# sheet1.net
KiCad netlist of a schematic drawn in Altium Designer
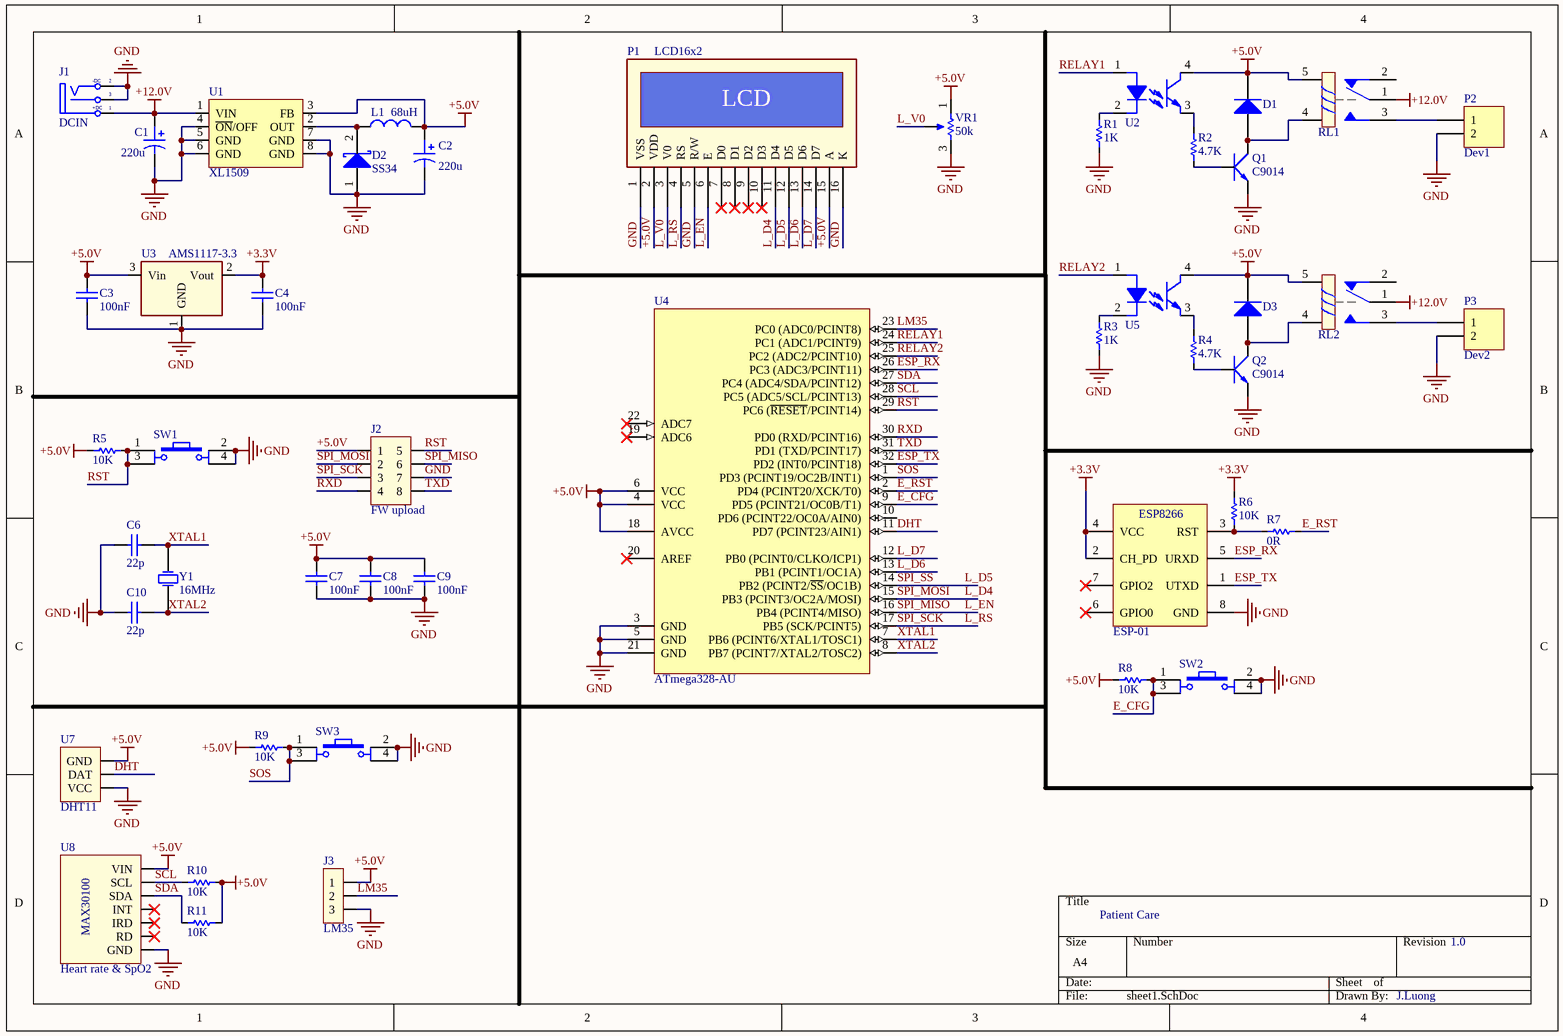
[diagram p0: sheet1.SchDoc]

(export (version "E")
  (design (tool "Eeschema 10.0.6"))
  (components
    (comp (ref "C1")
      (value "220u")
      (footprint "CAP_SMD_7343")
      (description "Polarized Capacitor")
      (fields (field (name "Comment") "Cap Pol") (field (name "PUBLISHER") "Altium Limited"))
      (libsource (lib "jmctvs") (part "Cap Pol"))
    )
    (comp (ref "C2")
      (value "220u")
      (footprint "CAP_SMD_7343")
      (description "Polarized Capacitor")
      (fields (field (name "Comment") "Cap Pol") (field (name "PUBLISHER") "Altium Limited"))
      (libsource (lib "jmctvs") (part "Cap Pol"))
    )
    (comp (ref "C3")
      (value "100nF")
      (footprint "CAP_SMD_0805")
      (description "Non-polarized Capacitor")
      (fields (field (name "Comment") "Cap Non-pol") (field (name "PUBLISHER") "Altium Limited"))
      (libsource (lib "jmctvs") (part "Cap Non-pol"))
    )
    (comp (ref "C4")
      (value "100nF")
      (footprint "CAP_SMD_0805")
      (description "Non-polarized Capacitor")
      (fields (field (name "Comment") "Cap Non-pol") (field (name "PUBLISHER") "Altium Limited"))
      (libsource (lib "jmctvs") (part "Cap Non-pol"))
    )
    (comp (ref "C6")
      (value "22p")
      (footprint "CAP_SMD_0805")
      (description "Non-polarized Capacitor")
      (fields (field (name "Comment") "Cap Non-pol") (field (name "PUBLISHER") "Altium Limited"))
      (libsource (lib "jmctvs") (part "Cap Non-pol"))
    )
    (comp (ref "C7")
      (value "100nF")
      (footprint "CAP_SMD_0805")
      (description "Non-polarized Capacitor")
      (fields (field (name "Comment") "Cap Non-pol") (field (name "PUBLISHER") "Altium Limited"))
      (libsource (lib "jmctvs") (part "Cap Non-pol"))
    )
    (comp (ref "C8")
      (value "100nF")
      (footprint "CAP_SMD_0805")
      (description "Non-polarized Capacitor")
      (fields (field (name "Comment") "Cap Non-pol") (field (name "PUBLISHER") "Altium Limited"))
      (libsource (lib "jmctvs") (part "Cap Non-pol"))
    )
    (comp (ref "C9")
      (value "100nF")
      (footprint "CAP_SMD_0805")
      (description "Non-polarized Capacitor")
      (fields (field (name "Comment") "Cap Non-pol") (field (name "PUBLISHER") "Altium Limited"))
      (libsource (lib "jmctvs") (part "Cap Non-pol"))
    )
    (comp (ref "C10")
      (value "22p")
      (footprint "CAP_SMD_0805")
      (description "Non-polarized Capacitor")
      (fields (field (name "Comment") "Cap Non-pol") (field (name "PUBLISHER") "Altium Limited"))
      (libsource (lib "jmctvs") (part "Cap Non-pol"))
    )
    (comp (ref "D1")
      (value "Diode Power")
      (footprint "DO-214AC,SMA")
      (fields (field (name "PUBLISHER") "Altium Limited"))
      (libsource (lib "jmctvs") (part "Diode Power"))
    )
    (comp (ref "D2")
      (value "SS34")
      (footprint "DO-214AC,SMA")
      (description "Schottky Rectifier")
      (fields (field (name "PUBLISHER") "Altium Limited"))
      (libsource (lib "jmctvs") (part "Diode Schottky"))
    )
    (comp (ref "D3")
      (value "Diode Power")
      (footprint "DO-214AC,SMA")
      (fields (field (name "PUBLISHER") "Altium Limited"))
      (libsource (lib "jmctvs") (part "Diode Power"))
    )
    (comp (ref "J1")
      (value "DCIN")
      (footprint "DC-IN")
      (description "Jac DC input")
      (libsource (lib "jmctvs") (part "DCIN"))
    )
    (comp (ref "J2")
      (value "FW upload")
      (footprint "JP4x2")
      (description "Connector 4x2")
      (libsource (lib "jmctvs") (part "JP4x2"))
    )
    (comp (ref "J3")
      (value "LM35")
      (footprint "JP3")
      (description "Jumper 3")
      (libsource (lib "jmctvs") (part "JP3"))
    )
    (comp (ref "L1")
      (value "68uH")
      (footprint "CDRH60")
      (description "Inductor")
      (fields (field (name "PUBLISHER") "Altium Limited"))
      (libsource (lib "jmctvs") (part "Inductor"))
    )
    (comp (ref "P1") (value "LCD16x2") (footprint "LCD16x2") (libsource (lib "jmctvs") (part "LCD Text")))
    (comp (ref "P2")
      (value "Dev1")
      (footprint "TBlock 2")
      (description "Header, 2-Pin")
      (fields (field (name "PUBLISHER") "Altium Limited"))
      (libsource (lib "jmctvs") (part "Header 2"))
    )
    (comp (ref "P3")
      (value "Dev2")
      (footprint "TBlock 2")
      (description "Header, 2-Pin")
      (fields (field (name "PUBLISHER") "Altium Limited"))
      (libsource (lib "jmctvs") (part "Header 2"))
    )
    (comp (ref "Q1")
      (value "C9014")
      (footprint "SOT23C")
      (description "NPN 600mW, EBC")
      (libsource (lib "jmctvs") (part "C9014"))
    )
    (comp (ref "Q2")
      (value "C9014")
      (footprint "SOT23C")
      (description "NPN 600mW, EBC")
      (libsource (lib "jmctvs") (part "C9014"))
    )
    (comp (ref "R1")
      (value "1K")
      (footprint "RES_SMD_0603")
      (description "Resistor")
      (fields (field (name "Comment") "RESISTOR") (field (name "PUBLISHER") "Altium Limited"))
      (libsource (lib "jmctvs") (part "RESISTOR"))
    )
    (comp (ref "R2")
      (value "4.7K")
      (footprint "RES_SMD_0603")
      (description "Resistor")
      (fields (field (name "Comment") "RESISTOR") (field (name "PUBLISHER") "Altium Limited"))
      (libsource (lib "jmctvs") (part "RESISTOR"))
    )
    (comp (ref "R3")
      (value "1K")
      (footprint "RES_SMD_0603")
      (description "Resistor")
      (fields (field (name "Comment") "RESISTOR") (field (name "PUBLISHER") "Altium Limited"))
      (libsource (lib "jmctvs") (part "RESISTOR"))
    )
    (comp (ref "R4")
      (value "4.7K")
      (footprint "RES_SMD_0603")
      (description "Resistor")
      (fields (field (name "Comment") "RESISTOR") (field (name "PUBLISHER") "Altium Limited"))
      (libsource (lib "jmctvs") (part "RESISTOR"))
    )
    (comp (ref "R5")
      (value "10K")
      (footprint "RES_SMD_0805")
      (description "Resistor")
      (fields (field (name "Comment") "RESISTOR") (field (name "PUBLISHER") "Altium Limited"))
      (libsource (lib "jmctvs") (part "RESISTOR"))
    )
    (comp (ref "R6")
      (value "10K")
      (footprint "RES_SMD_0805")
      (description "Resistor")
      (fields (field (name "Comment") "RESISTOR") (field (name "PUBLISHER") "Altium Limited"))
      (libsource (lib "jmctvs") (part "RESISTOR"))
    )
    (comp (ref "R7")
      (value "0R")
      (footprint "RES_SMD_0805")
      (description "Resistor")
      (fields (field (name "Comment") "RESISTOR") (field (name "PUBLISHER") "Altium Limited"))
      (libsource (lib "jmctvs") (part "RESISTOR"))
    )
    (comp (ref "R8")
      (value "10K")
      (footprint "RES_SMD_0805")
      (description "Resistor")
      (fields (field (name "Comment") "RESISTOR") (field (name "PUBLISHER") "Altium Limited"))
      (libsource (lib "jmctvs") (part "RESISTOR"))
    )
    (comp (ref "R9")
      (value "10K")
      (footprint "RES_SMD_0805")
      (description "Resistor")
      (fields (field (name "Comment") "RESISTOR") (field (name "PUBLISHER") "Altium Limited"))
      (libsource (lib "jmctvs") (part "RESISTOR"))
    )
    (comp (ref "R10")
      (value "10K")
      (footprint "RES_SMD_0805")
      (description "Resistor")
      (fields (field (name "Comment") "RESISTOR") (field (name "PUBLISHER") "Altium Limited"))
      (libsource (lib "jmctvs") (part "RESISTOR"))
    )
    (comp (ref "R11")
      (value "10K")
      (footprint "RES_SMD_0805")
      (description "Resistor")
      (fields (field (name "Comment") "RESISTOR") (field (name "PUBLISHER") "Altium Limited"))
      (libsource (lib "jmctvs") (part "RESISTOR"))
    )
    (comp (ref "RL1")
      (value "RELAY5V")
      (footprint "RELAY5")
      (description "Ro le 5V")
      (fields (field (name "PUBLISHER") "Hoang Nguyen"))
      (libsource (lib "jmctvs") (part "RELAY5V"))
    )
    (comp (ref "RL2")
      (value "RELAY5V")
      (footprint "RELAY5")
      (description "Ro le 5V")
      (fields (field (name "PUBLISHER") "Hoang Nguyen"))
      (libsource (lib "jmctvs") (part "RELAY5V"))
    )
    (comp (ref "SW1")
      (value "SW")
      (footprint "SW4")
      (description "Switch button 4 pin")
      (libsource (lib "jmctvs") (part "SW4"))
    )
    (comp (ref "SW2")
      (value "SW")
      (footprint "SW4")
      (description "Switch button 4 pin")
      (libsource (lib "jmctvs") (part "SW4"))
    )
    (comp (ref "SW3")
      (value "SW")
      (footprint "SW4_12MM")
      (description "Switch button 4 pin")
      (libsource (lib "jmctvs") (part "SW4"))
    )
    (comp (ref "U1") (value "XL1509") (footprint "SOP8") (libsource (lib "jmctvs") (part "XL1509")))
    (comp (ref "U2")
      (value "PC817")
      (footprint "DIP4")
      (description "Opto Couple")
      (fields (field (name "PUBLISHER") "Hoang Nguyen"))
      (libsource (lib "jmctvs") (part "PC817"))
    )
    (comp (ref "U3")
      (value "AMS1117-3.3")
      (footprint "SOT223")
      (description "Regulator SMD Chip")
      (fields (field (name "DESIGNED BY") "John MacTavish"))
      (libsource (lib "jmctvs") (part "AMS1117"))
    )
    (comp (ref "U4")
      (value "ATmega328-AU")
      (footprint "TQFP32A")
      (libsource (lib "jmctvs") (part "ATmega328-AU"))
    )
    (comp (ref "U5")
      (value "PC817")
      (footprint "DIP4")
      (description "Opto Couple")
      (fields (field (name "PUBLISHER") "Hoang Nguyen"))
      (libsource (lib "jmctvs") (part "PC817"))
    )
    (comp (ref "U6")
      (value "ESP-01")
      (footprint "ESP8266")
      (description "ESP-12 Wi-Fi Module")
      (libsource (lib "jmctvs") (part "ESP8266-01"))
    )
    (comp (ref "U7") (value "DHT11") (footprint "DHT11") (libsource (lib "jmctvs") (part "DHT11")))
    (comp (ref "U8")
      (value "Heart rate & SpO2")
      (footprint "MAX30100")
      (libsource (lib "jmctvs") (part "MAX30100"))
    )
    (comp (ref "VR1")
      (value "50k")
      (footprint "VRes-R")
      (description "Variable Resistor")
      (fields (field (name "PUBLISHER") "Altium Limited"))
      (libsource (lib "jmctvs") (part "RES-VAR"))
    )
    (comp (ref "Y1")
      (value "16MHz")
      (footprint "XTAL")
      (description "Crystal Oscillator")
      (fields (field (name "PUBLISHER") "Altium Limited"))
      (libsource (lib "jmctvs") (part "XTAL"))
    )
  )
  (nets
    (net (code "1") (name "+3.3V") (class "Default")
      (node (ref "C4") (pin "2") (pinfunction "2_2") (pintype "passive"))
      (node (ref "R6") (pin "1") (pinfunction "1_1") (pintype "passive"))
      (node (ref "U3") (pin "2") (pinfunction "Vout_2") (pintype "passive"))
      (node (ref "U6") (pin "2") (pinfunction "CH_PD_2") (pintype "passive"))
      (node (ref "U6") (pin "4") (pinfunction "VCC_4") (pintype "passive"))
    )
    (net (code "2") (name "+5.0V") (class "Default")
      (node (ref "C2") (pin "1") (pinfunction "1_1") (pintype "passive"))
      (node (ref "C3") (pin "2") (pinfunction "2_2") (pintype "passive"))
      (node (ref "C7") (pin "2") (pinfunction "2_2") (pintype "passive"))
      (node (ref "C8") (pin "2") (pinfunction "2_2") (pintype "passive"))
      (node (ref "C9") (pin "2") (pinfunction "2_2") (pintype "passive"))
      (node (ref "D1") (pin "2") (pinfunction "K_2") (pintype "passive"))
      (node (ref "D3") (pin "2") (pinfunction "K_2") (pintype "passive"))
      (node (ref "J2") (pin "1") (pinfunction "1_1") (pintype "passive"))
      (node (ref "J3") (pin "1") (pinfunction "1_1") (pintype "passive"))
      (node (ref "L1") (pin "2") (pinfunction "2_2") (pintype "passive"))
      (node (ref "P1") (pin "15") (pinfunction "A_15") (pintype "passive"))
      (node (ref "P1") (pin "2") (pinfunction "VDD_2") (pintype "passive"))
      (node (ref "R10") (pin "1") (pinfunction "1_1") (pintype "passive"))
      (node (ref "R11") (pin "1") (pinfunction "1_1") (pintype "passive"))
      (node (ref "R5") (pin "2") (pinfunction "2_2") (pintype "passive"))
      (node (ref "R8") (pin "2") (pinfunction "2_2") (pintype "passive"))
      (node (ref "R9") (pin "2") (pinfunction "2_2") (pintype "passive"))
      (node (ref "RL1") (pin "5") (pinfunction "5_5") (pintype "passive"))
      (node (ref "RL2") (pin "5") (pinfunction "5_5") (pintype "passive"))
      (node (ref "U1") (pin "3") (pinfunction "FB_3") (pintype "passive"))
      (node (ref "U2") (pin "4") (pinfunction "4_4") (pintype "passive"))
      (node (ref "U3") (pin "3") (pinfunction "Vin_3") (pintype "passive"))
      (node (ref "U4") (pin "18") (pinfunction "AVCC_18") (pintype "power_in"))
      (node (ref "U4") (pin "4") (pinfunction "VCC_4") (pintype "power_in"))
      (node (ref "U4") (pin "6") (pinfunction "VCC_6") (pintype "power_in"))
      (node (ref "U5") (pin "4") (pinfunction "4_4") (pintype "passive"))
      (node (ref "U7") (pin "1") (pinfunction "GND_1") (pintype "passive"))
      (node (ref "U8") (pin "1") (pinfunction "VIN_1") (pintype "passive"))
      (node (ref "VR1") (pin "1") (pinfunction "1_1") (pintype "passive"))
    )
    (net (code "3") (name "+12.0V") (class "Default")
      (node (ref "C1") (pin "1") (pinfunction "1_1") (pintype "passive"))
      (node (ref "J1") (pin "1") (pinfunction "T_1") (pintype "passive"))
      (node (ref "RL1") (pin "1") (pinfunction "1_1") (pintype "passive"))
      (node (ref "RL2") (pin "1") (pinfunction "1_1") (pintype "passive"))
      (node (ref "U1") (pin "1") (pinfunction "VIN_1") (pintype "passive"))
    )
    (net (code "4") (name "/DHT") (class "Default")
      (node (ref "U4") (pin "11") (pinfunction "PD7_(PCINT23/AIN1)_11") (pintype "bidirectional"))
      (node (ref "U7") (pin "2") (pinfunction "DAT_2") (pintype "passive"))
    )
    (net (code "5") (name "/ESP_RX") (class "Default")
      (node (ref "U4") (pin "26") (pinfunction "PC3_(ADC3/PCINT11)_26") (pintype "bidirectional"))
      (node (ref "U6") (pin "5") (pinfunction "URXD_5") (pintype "passive"))
    )
    (net (code "6") (name "/ESP_TX") (class "Default")
      (node (ref "U4") (pin "32") (pinfunction "PD2_(INT0/PCINT18)_32") (pintype "bidirectional"))
      (node (ref "U6") (pin "1") (pinfunction "UTXD_1") (pintype "passive"))
    )
    (net (code "7") (name "/E_CFG") (class "Default")
      (node (ref "R8") (pin "1") (pinfunction "1_1") (pintype "passive"))
      (node (ref "SW2") (pin "1") (pintype "passive"))
      (node (ref "SW2") (pin "3") (pintype "passive"))
      (node (ref "U4") (pin "9") (pinfunction "PD5_(PCINT21/OC0B/T1)_9") (pintype "bidirectional"))
    )
    (net (code "8") (name "/E_RST") (class "Default")
      (node (ref "R7") (pin "2") (pinfunction "2_2") (pintype "passive"))
      (node (ref "U4") (pin "2") (pinfunction "PD4_(PCINT20/XCK/T0)_2") (pintype "bidirectional"))
    )
    (net (code "9") (name "/LM35") (class "Default")
      (node (ref "J3") (pin "2") (pinfunction "2_2") (pintype "passive"))
      (node (ref "U4") (pin "23") (pinfunction "PC0_(ADC0/PCINT8)_23") (pintype "bidirectional"))
    )
    (net (code "10") (name "/L_D4") (class "Default")
      (node (ref "J2") (pin "2") (pinfunction "2_2") (pintype "passive"))
      (node (ref "P1") (pin "11") (pinfunction "D4_11") (pintype "passive"))
      (node (ref "U4") (pin "15") (pinfunction "PB3_(PCINT3/OC2A/MOSI)_15") (pintype "bidirectional"))
    )
    (net (code "11") (name "/L_D5") (class "Default")
      (node (ref "P1") (pin "12") (pinfunction "D5_12") (pintype "passive"))
      (node (ref "U4") (pin "14") (pinfunction "PB2_(PCINT2/~{SS}/OC1B)_14") (pintype "bidirectional"))
    )
    (net (code "12") (name "/L_D6") (class "Default")
      (node (ref "P1") (pin "13") (pinfunction "D6_13") (pintype "passive"))
      (node (ref "U4") (pin "13") (pinfunction "PB1_(PCINT1/OC1A)_13") (pintype "bidirectional"))
    )
    (net (code "13") (name "/L_D7") (class "Default")
      (node (ref "P1") (pin "14") (pinfunction "D7_14") (pintype "passive"))
      (node (ref "U4") (pin "12") (pinfunction "PB0_(PCINT0/CLKO/ICP1)_12") (pintype "bidirectional"))
    )
    (net (code "14") (name "/L_EN") (class "Default")
      (node (ref "J2") (pin "6") (pinfunction "6_6") (pintype "passive"))
      (node (ref "P1") (pin "6") (pinfunction "E_6") (pintype "passive"))
      (node (ref "U4") (pin "16") (pinfunction "PB4_(PCINT4/MISO)_16") (pintype "bidirectional"))
    )
    (net (code "15") (name "/L_RS") (class "Default")
      (node (ref "J2") (pin "3") (pinfunction "3_3") (pintype "passive"))
      (node (ref "P1") (pin "4") (pinfunction "RS_4") (pintype "passive"))
      (node (ref "U4") (pin "17") (pinfunction "PB5_(SCK/PCINT5)_17") (pintype "bidirectional"))
    )
    (net (code "16") (name "/L_V0") (class "Default")
      (node (ref "P1") (pin "3") (pinfunction "V0_3") (pintype "passive"))
      (node (ref "VR1") (pin "2") (pinfunction "2_2") (pintype "passive"))
    )
    (net (code "17") (name "/RELAY1") (class "Default")
      (node (ref "U2") (pin "1") (pinfunction "1_1") (pintype "passive"))
      (node (ref "U4") (pin "24") (pinfunction "PC1_(ADC1/PCINT9)_24") (pintype "bidirectional"))
    )
    (net (code "18") (name "/RELAY2") (class "Default")
      (node (ref "U4") (pin "25") (pinfunction "PC2_(ADC2/PCINT10)_25") (pintype "bidirectional"))
      (node (ref "U5") (pin "1") (pinfunction "1_1") (pintype "passive"))
    )
    (net (code "19") (name "/RST") (class "Default")
      (node (ref "J2") (pin "5") (pinfunction "5_5") (pintype "passive"))
      (node (ref "R5") (pin "1") (pinfunction "1_1") (pintype "passive"))
      (node (ref "SW1") (pin "1") (pintype "passive"))
      (node (ref "SW1") (pin "3") (pintype "passive"))
      (node (ref "U4") (pin "29") (pinfunction "PC6_(~{RESET}/PCINT14)_29") (pintype "bidirectional"))
    )
    (net (code "20") (name "/RXD") (class "Default")
      (node (ref "J2") (pin "4") (pinfunction "4_4") (pintype "passive"))
      (node (ref "U4") (pin "30") (pinfunction "PD0_(RXD/PCINT16)_30") (pintype "bidirectional"))
    )
    (net (code "21") (name "/SCL") (class "Default")
      (node (ref "R10") (pin "2") (pinfunction "2_2") (pintype "passive"))
      (node (ref "U4") (pin "28") (pinfunction "PC5_(ADC5/SCL/PCINT13)_28") (pintype "bidirectional"))
      (node (ref "U8") (pin "2") (pinfunction "SCL_2") (pintype "passive"))
    )
    (net (code "22") (name "/SDA") (class "Default")
      (node (ref "R11") (pin "2") (pinfunction "2_2") (pintype "passive"))
      (node (ref "U4") (pin "27") (pinfunction "PC4_(ADC4/SDA/PCINT12)_27") (pintype "bidirectional"))
      (node (ref "U8") (pin "3") (pinfunction "SDA_3") (pintype "passive"))
    )
    (net (code "23") (name "/SOS") (class "Default")
      (node (ref "R9") (pin "1") (pinfunction "1_1") (pintype "passive"))
      (node (ref "SW3") (pin "1") (pintype "passive"))
      (node (ref "SW3") (pin "3") (pintype "passive"))
      (node (ref "U4") (pin "1") (pinfunction "PD3_(PCINT19/OC2B/INT1)_1") (pintype "bidirectional"))
    )
    (net (code "24") (name "/TXD") (class "Default")
      (node (ref "J2") (pin "8") (pinfunction "8_8") (pintype "passive"))
      (node (ref "U4") (pin "31") (pinfunction "PD1_(TXD/PCINT17)_31") (pintype "bidirectional"))
    )
    (net (code "25") (name "/XTAL1") (class "Default")
      (node (ref "C6") (pin "2") (pinfunction "2_2") (pintype "passive"))
      (node (ref "U4") (pin "7") (pinfunction "PB6_(PCINT6/XTAL1/TOSC1)_7") (pintype "bidirectional"))
      (node (ref "Y1") (pin "2") (pinfunction "OSC2_2") (pintype "passive"))
    )
    (net (code "26") (name "/XTAL2") (class "Default")
      (node (ref "C10") (pin "2") (pinfunction "2_2") (pintype "passive"))
      (node (ref "U4") (pin "8") (pinfunction "PB7_(PCINT7/XTAL2/TOSC2)_8") (pintype "bidirectional"))
      (node (ref "Y1") (pin "1") (pinfunction "OSC1_1") (pintype "passive"))
    )
    (net (code "27") (name "GND") (class "Default")
      (node (ref "C1") (pin "2") (pinfunction "2_2") (pintype "passive"))
      (node (ref "C10") (pin "1") (pinfunction "1_1") (pintype "passive"))
      (node (ref "C2") (pin "2") (pinfunction "2_2") (pintype "passive"))
      (node (ref "C3") (pin "1") (pinfunction "1_1") (pintype "passive"))
      (node (ref "C4") (pin "1") (pinfunction "1_1") (pintype "passive"))
      (node (ref "C6") (pin "1") (pinfunction "1_1") (pintype "passive"))
      (node (ref "C7") (pin "1") (pinfunction "1_1") (pintype "passive"))
      (node (ref "C8") (pin "1") (pinfunction "1_1") (pintype "passive"))
      (node (ref "C9") (pin "1") (pinfunction "1_1") (pintype "passive"))
      (node (ref "D2") (pin "1") (pinfunction "A_1") (pintype "passive"))
      (node (ref "J1") (pin "2") (pinfunction "TN_2") (pintype "passive"))
      (node (ref "J1") (pin "3") (pinfunction "S_3") (pintype "power_in"))
      (node (ref "J2") (pin "7") (pinfunction "7_7") (pintype "passive"))
      (node (ref "J3") (pin "3") (pinfunction "3_3") (pintype "passive"))
      (node (ref "P1") (pin "1") (pinfunction "VSS_1") (pintype "passive"))
      (node (ref "P1") (pin "16") (pinfunction "K_16") (pintype "passive"))
      (node (ref "P1") (pin "5") (pinfunction "R/W_5") (pintype "passive"))
      (node (ref "P2") (pin "2") (pinfunction "2_2") (pintype "passive"))
      (node (ref "P3") (pin "2") (pinfunction "2_2") (pintype "passive"))
      (node (ref "Q1") (pin "1") (pinfunction "E_1") (pintype "passive"))
      (node (ref "Q2") (pin "1") (pinfunction "E_1") (pintype "passive"))
      (node (ref "R1") (pin "1") (pinfunction "1_1") (pintype "passive"))
      (node (ref "R3") (pin "1") (pinfunction "1_1") (pintype "passive"))
      (node (ref "SW1") (pin "2") (pintype "passive"))
      (node (ref "SW1") (pin "4") (pintype "passive"))
      (node (ref "SW2") (pin "2") (pintype "passive"))
      (node (ref "SW2") (pin "4") (pintype "passive"))
      (node (ref "SW3") (pin "2") (pintype "passive"))
      (node (ref "SW3") (pin "4") (pintype "passive"))
      (node (ref "U1") (pin "4") (pinfunction "~{ON}/OFF_4") (pintype "passive"))
      (node (ref "U1") (pin "5") (pinfunction "GND_5") (pintype "passive"))
      (node (ref "U1") (pin "6") (pinfunction "GND_6") (pintype "passive"))
      (node (ref "U1") (pin "7") (pinfunction "GND_7") (pintype "passive"))
      (node (ref "U1") (pin "8") (pinfunction "GND_8") (pintype "passive"))
      (node (ref "U3") (pin "1") (pinfunction "GND_1") (pintype "passive"))
      (node (ref "U4") (pin "21") (pinfunction "GND_21") (pintype "power_in"))
      (node (ref "U4") (pin "3") (pinfunction "GND_3") (pintype "power_in"))
      (node (ref "U4") (pin "5") (pinfunction "GND_5") (pintype "power_in"))
      (node (ref "U6") (pin "8") (pinfunction "GND_8") (pintype "passive"))
      (node (ref "U7") (pin "3") (pinfunction "VCC_3") (pintype "passive"))
      (node (ref "U8") (pin "7") (pinfunction "GND_7") (pintype "passive"))
      (node (ref "VR1") (pin "3") (pinfunction "3_3") (pintype "passive"))
    )
    (net (code "28") (name "Net-(D1-A)") (class "Default")
      (node (ref "D1") (pin "1") (pinfunction "A_1") (pintype "passive"))
      (node (ref "Q1") (pin "3") (pinfunction "C_3") (pintype "passive"))
      (node (ref "RL1") (pin "4") (pinfunction "4_4") (pintype "passive"))
    )
    (net (code "29") (name "Net-(D2-4)") (class "Default")
      (node (ref "D2") (pin "2") (pinfunction "4_2") (pintype "passive"))
      (node (ref "L1") (pin "1") (pinfunction "1_1") (pintype "passive"))
      (node (ref "U1") (pin "2") (pinfunction "OUT_2") (pintype "passive"))
    )
    (net (code "30") (name "Net-(D3-A)") (class "Default")
      (node (ref "D3") (pin "1") (pinfunction "A_1") (pintype "passive"))
      (node (ref "Q2") (pin "3") (pinfunction "C_3") (pintype "passive"))
      (node (ref "RL2") (pin "4") (pinfunction "4_4") (pintype "passive"))
    )
    (net (code "31") (name "Net-(P2-Pad1)") (class "Default")
      (node (ref "P2") (pin "1") (pinfunction "1_1") (pintype "passive"))
      (node (ref "RL1") (pin "3") (pinfunction "3_3") (pintype "passive"))
    )
    (net (code "32") (name "Net-(P3-Pad1)") (class "Default")
      (node (ref "P3") (pin "1") (pinfunction "1_1") (pintype "passive"))
      (node (ref "RL2") (pin "3") (pinfunction "3_3") (pintype "passive"))
    )
    (net (code "33") (name "Net-(Q1-B)") (class "Default")
      (node (ref "Q1") (pin "2") (pinfunction "B_2") (pintype "passive"))
      (node (ref "R2") (pin "1") (pinfunction "1_1") (pintype "passive"))
    )
    (net (code "34") (name "Net-(Q2-B)") (class "Default")
      (node (ref "Q2") (pin "2") (pinfunction "B_2") (pintype "passive"))
      (node (ref "R4") (pin "1") (pinfunction "1_1") (pintype "passive"))
    )
    (net (code "35") (name "Net-(R1-Pad2)") (class "Default")
      (node (ref "R1") (pin "2") (pinfunction "2_2") (pintype "passive"))
      (node (ref "U2") (pin "2") (pinfunction "2_2") (pintype "passive"))
    )
    (net (code "36") (name "Net-(R2-Pad2)") (class "Default")
      (node (ref "R2") (pin "2") (pinfunction "2_2") (pintype "passive"))
      (node (ref "U2") (pin "3") (pinfunction "3_3") (pintype "passive"))
    )
    (net (code "37") (name "Net-(R3-Pad2)") (class "Default")
      (node (ref "R3") (pin "2") (pinfunction "2_2") (pintype "passive"))
      (node (ref "U5") (pin "2") (pinfunction "2_2") (pintype "passive"))
    )
    (net (code "38") (name "Net-(R4-Pad2)") (class "Default")
      (node (ref "R4") (pin "2") (pinfunction "2_2") (pintype "passive"))
      (node (ref "U5") (pin "3") (pinfunction "3_3") (pintype "passive"))
    )
    (net (code "39") (name "Net-(U6-RST)") (class "Default")
      (node (ref "R6") (pin "2") (pinfunction "2_2") (pintype "passive"))
      (node (ref "R7") (pin "1") (pinfunction "1_1") (pintype "passive"))
      (node (ref "U6") (pin "3") (pinfunction "RST_3") (pintype "passive"))
    )
    (net (code "40") (name "unconnected-(P1-D0-Pad7)") (class "Default")
      (node (ref "P1") (pin "7") (pinfunction "D0_7") (pintype "passive+no_connect"))
    )
    (net (code "41") (name "unconnected-(P1-D1-Pad8)") (class "Default")
      (node (ref "P1") (pin "8") (pinfunction "D1_8") (pintype "passive+no_connect"))
    )
    (net (code "42") (name "unconnected-(P1-D2-Pad9)") (class "Default")
      (node (ref "P1") (pin "9") (pinfunction "D2_9") (pintype "passive+no_connect"))
    )
    (net (code "43") (name "unconnected-(P1-D3-Pad10)") (class "Default")
      (node (ref "P1") (pin "10") (pinfunction "D3_10") (pintype "passive+no_connect"))
    )
    (net (code "44") (name "unconnected-(RL1-Pad2)") (class "Default")
      (node (ref "RL1") (pin "2") (pinfunction "2_2") (pintype "passive"))
    )
    (net (code "45") (name "unconnected-(RL2-Pad2)") (class "Default")
      (node (ref "RL2") (pin "2") (pinfunction "2_2") (pintype "passive"))
    )
    (net (code "46") (name "unconnected-(U4-ADC6-Pad19)") (class "Default")
      (node (ref "U4") (pin "19") (pinfunction "ADC6_19") (pintype "input+no_connect"))
    )
    (net (code "47") (name "unconnected-(U4-ADC7-Pad22)") (class "Default")
      (node (ref "U4") (pin "22") (pinfunction "ADC7_22") (pintype "input+no_connect"))
    )
    (net (code "48") (name "unconnected-(U4-AREF-Pad20)") (class "Default")
      (node (ref "U4") (pin "20") (pinfunction "AREF_20") (pintype "passive+no_connect"))
    )
    (net (code "49") (name "unconnected-(U4-PD6_(PCINT22{slash}OC0A{slash}AIN0)-Pad10)") (class "Default")
      (node (ref "U4") (pin "10") (pinfunction "PD6_(PCINT22/OC0A/AIN0)_10") (pintype "bidirectional"))
    )
    (net (code "50") (name "unconnected-(U6-GPIO0-Pad6)") (class "Default")
      (node (ref "U6") (pin "6") (pinfunction "GPIO0_6") (pintype "passive+no_connect"))
    )
    (net (code "51") (name "unconnected-(U6-GPIO2-Pad7)") (class "Default")
      (node (ref "U6") (pin "7") (pinfunction "GPIO2_7") (pintype "passive+no_connect"))
    )
    (net (code "52") (name "unconnected-(U8-INT-Pad4)") (class "Default")
      (node (ref "U8") (pin "4") (pinfunction "INT_4") (pintype "passive+no_connect"))
    )
    (net (code "53") (name "unconnected-(U8-IRD-Pad5)") (class "Default")
      (node (ref "U8") (pin "5") (pinfunction "IRD_5") (pintype "passive+no_connect"))
    )
    (net (code "54") (name "unconnected-(U8-RD-Pad6)") (class "Default")
      (node (ref "U8") (pin "6") (pinfunction "RD_6") (pintype "passive+no_connect"))
    )
  )
)
